# TYPEC.net
KiCad netlist of a schematic drawn in Altium Designer
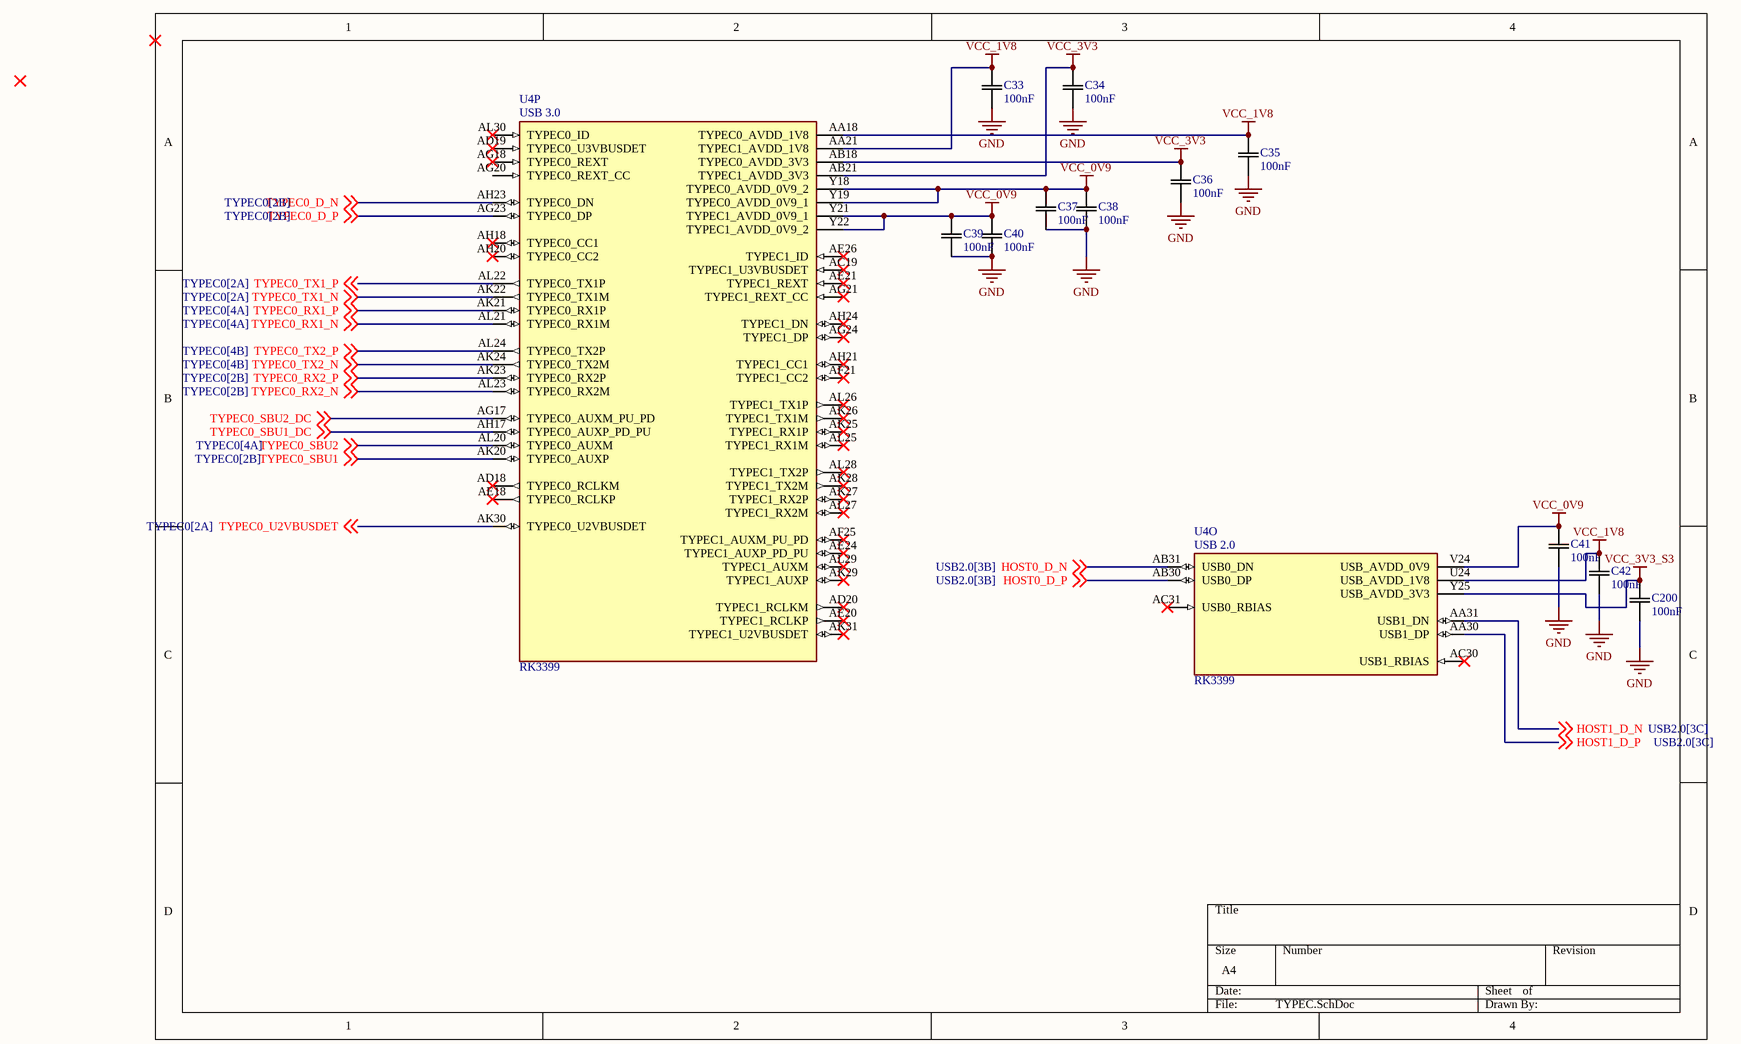
[diagram p0: TYPEC.SchDoc]

(export (version "E")
  (design (tool "Eeschema 10.0.6"))
  (components
    (comp (ref "C33")
      (value "100nF")
      (footprint "CAP_1005_TDK")
      (description "Description")
      (fields
        (field (name "MANUFACTURER_PART_NUMBER") "C1005X7R1H104M050BB")
        (field (name "COPYRIGHT") "Copyright (C) 2025 Ultra Librarian. All rights reserved.")
      )
      (libsource (lib "C1005X7R1H104M050BB") (part "C1005X7R1H104M050BB"))
    )
    (comp (ref "C34")
      (value "100nF")
      (footprint "CAP_1005_TDK")
      (description "Description")
      (fields
        (field (name "MANUFACTURER_PART_NUMBER") "C1005X7R1H104M050BB")
        (field (name "COPYRIGHT") "Copyright (C) 2025 Ultra Librarian. All rights reserved.")
      )
      (libsource (lib "C1005X7R1H104M050BB") (part "C1005X7R1H104M050BB"))
    )
    (comp (ref "C35")
      (value "100nF")
      (footprint "CAP_1005_TDK")
      (description "Description")
      (fields
        (field (name "MANUFACTURER_PART_NUMBER") "C1005X7R1H104M050BB")
        (field (name "COPYRIGHT") "Copyright (C) 2025 Ultra Librarian. All rights reserved.")
      )
      (libsource (lib "C1005X7R1H104M050BB") (part "C1005X7R1H104M050BB"))
    )
    (comp (ref "C36")
      (value "100nF")
      (footprint "CAP_1005_TDK")
      (description "Description")
      (fields
        (field (name "MANUFACTURER_PART_NUMBER") "C1005X7R1H104M050BB")
        (field (name "COPYRIGHT") "Copyright (C) 2025 Ultra Librarian. All rights reserved.")
      )
      (libsource (lib "C1005X7R1H104M050BB") (part "C1005X7R1H104M050BB"))
    )
    (comp (ref "C37")
      (value "100nF")
      (footprint "CAP_1005_TDK")
      (description "Description")
      (fields
        (field (name "MANUFACTURER_PART_NUMBER") "C1005X7R1H104M050BB")
        (field (name "COPYRIGHT") "Copyright (C) 2025 Ultra Librarian. All rights reserved.")
      )
      (libsource (lib "C1005X7R1H104M050BB") (part "C1005X7R1H104M050BB"))
    )
    (comp (ref "C38")
      (value "100nF")
      (footprint "CAP_1005_TDK")
      (description "Description")
      (fields
        (field (name "MANUFACTURER_PART_NUMBER") "C1005X7R1H104M050BB")
        (field (name "COPYRIGHT") "Copyright (C) 2025 Ultra Librarian. All rights reserved.")
      )
      (libsource (lib "C1005X7R1H104M050BB") (part "C1005X7R1H104M050BB"))
    )
    (comp (ref "C39")
      (value "100nF")
      (footprint "CAP_1005_TDK")
      (description "Description")
      (fields
        (field (name "MANUFACTURER_PART_NUMBER") "C1005X7R1H104M050BB")
        (field (name "COPYRIGHT") "Copyright (C) 2025 Ultra Librarian. All rights reserved.")
      )
      (libsource (lib "C1005X7R1H104M050BB") (part "C1005X7R1H104M050BB"))
    )
    (comp (ref "C40")
      (value "100nF")
      (footprint "CAP_1005_TDK")
      (description "Description")
      (fields
        (field (name "MANUFACTURER_PART_NUMBER") "C1005X7R1H104M050BB")
        (field (name "COPYRIGHT") "Copyright (C) 2025 Ultra Librarian. All rights reserved.")
      )
      (libsource (lib "C1005X7R1H104M050BB") (part "C1005X7R1H104M050BB"))
    )
    (comp (ref "C41")
      (value "100nF")
      (footprint "CAP_1005_TDK")
      (description "Description")
      (fields
        (field (name "MANUFACTURER_PART_NUMBER") "C1005X7R1H104M050BB")
        (field (name "COPYRIGHT") "Copyright (C) 2025 Ultra Librarian. All rights reserved.")
      )
      (libsource (lib "C1005X7R1H104M050BB") (part "C1005X7R1H104M050BB"))
    )
    (comp (ref "C42")
      (value "100nF")
      (footprint "CAP_1005_TDK")
      (description "Description")
      (fields
        (field (name "MANUFACTURER_PART_NUMBER") "C1005X7R1H104M050BB")
        (field (name "COPYRIGHT") "Copyright (C) 2025 Ultra Librarian. All rights reserved.")
      )
      (libsource (lib "C1005X7R1H104M050BB") (part "C1005X7R1H104M050BB"))
    )
    (comp (ref "C200")
      (value "100nF")
      (footprint "CAP_1005_TDK")
      (description "Description")
      (fields
        (field (name "MANUFACTURER_PART_NUMBER") "C1005X7R1H104M050BB")
        (field (name "COPYRIGHT") "Copyright (C) 2025 Ultra Librarian. All rights reserved.")
      )
      (libsource (lib "C1005X7R1H104M050BB") (part "C1005X7R1H104M050BB"))
    )
    (comp (ref "U4")
      (value "RK3399")
      (footprint "BGA828C65P31X31_2100X2100X161N")
      (description "RK3399 ROCK Pi 4 Model A 2GB - ARMÂ® CortexÂ®-A53, CortexÂ®-A72 MPU Embedded Evaluation Board")
      (fields (field (name "MF") "Rockchip"))
      (libsource (lib "RK3399") (part "RK3399"))
    )
  )
  (nets
    (net (code "1") (name "GND") (class "Default")
      (node (ref "C200") (pin "2") (pinfunction "2_2") (pintype "passive"))
      (node (ref "C33") (pin "2") (pinfunction "2_2") (pintype "passive"))
      (node (ref "C34") (pin "2") (pinfunction "2_2") (pintype "passive"))
      (node (ref "C35") (pin "2") (pinfunction "2_2") (pintype "passive"))
      (node (ref "C36") (pin "2") (pinfunction "2_2") (pintype "passive"))
      (node (ref "C37") (pin "2") (pinfunction "2_2") (pintype "passive"))
      (node (ref "C38") (pin "2") (pinfunction "2_2") (pintype "passive"))
      (node (ref "C39") (pin "2") (pinfunction "2_2") (pintype "passive"))
      (node (ref "C40") (pin "2") (pinfunction "2_2") (pintype "passive"))
      (node (ref "C41") (pin "2") (pinfunction "2_2") (pintype "passive"))
      (node (ref "C42") (pin "2") (pinfunction "2_2") (pintype "passive"))
    )
    (net (code "2") (name "HOST0_D_N") (class "Default")
      (node (ref "U4") (pin "AB31") (pinfunction "USB0_DN_AB31") (pintype "bidirectional"))
    )
    (net (code "3") (name "HOST0_D_P") (class "Default")
      (node (ref "U4") (pin "AB30") (pinfunction "USB0_DP_AB30") (pintype "bidirectional"))
    )
    (net (code "4") (name "HOST1_D_N") (class "Default")
      (node (ref "U4") (pin "AA31") (pinfunction "USB1_DN_AA31") (pintype "bidirectional"))
    )
    (net (code "5") (name "HOST1_D_P") (class "Default")
      (node (ref "U4") (pin "AA30") (pinfunction "USB1_DP_AA30") (pintype "bidirectional"))
    )
    (net (code "6") (name "TYPEC0_D_N") (class "Default")
      (node (ref "U4") (pin "AH23") (pinfunction "TYPEC0_DN_AH23") (pintype "bidirectional"))
    )
    (net (code "7") (name "TYPEC0_D_P") (class "Default")
      (node (ref "U4") (pin "AG23") (pinfunction "TYPEC0_DP_AG23") (pintype "bidirectional"))
    )
    (net (code "8") (name "TYPEC0_RX1_N") (class "Default")
      (node (ref "U4") (pin "AL21") (pinfunction "TYPEC0_RX1M_AL21") (pintype "bidirectional"))
    )
    (net (code "9") (name "TYPEC0_RX1_P") (class "Default")
      (node (ref "U4") (pin "AK21") (pinfunction "TYPEC0_RX1P_AK21") (pintype "bidirectional"))
    )
    (net (code "10") (name "TYPEC0_RX2_N") (class "Default")
      (node (ref "U4") (pin "AL23") (pinfunction "TYPEC0_RX2M_AL23") (pintype "bidirectional"))
    )
    (net (code "11") (name "TYPEC0_RX2_P") (class "Default")
      (node (ref "U4") (pin "AK23") (pinfunction "TYPEC0_RX2P_AK23") (pintype "bidirectional"))
    )
    (net (code "12") (name "TYPEC0_SBU1") (class "Default")
      (node (ref "U4") (pin "AK20") (pinfunction "TYPEC0_AUXP_AK20") (pintype "bidirectional"))
    )
    (net (code "13") (name "TYPEC0_SBU1_DC") (class "Default")
      (node (ref "U4") (pin "AH17") (pinfunction "TYPEC0_AUXP_PD_PU_AH17") (pintype "bidirectional"))
    )
    (net (code "14") (name "TYPEC0_SBU2") (class "Default")
      (node (ref "U4") (pin "AL20") (pinfunction "TYPEC0_AUXM_AL20") (pintype "bidirectional"))
    )
    (net (code "15") (name "TYPEC0_SBU2_DC") (class "Default")
      (node (ref "U4") (pin "AG17") (pinfunction "TYPEC0_AUXM_PU_PD_AG17") (pintype "bidirectional"))
    )
    (net (code "16") (name "TYPEC0_TX1_N") (class "Default")
      (node (ref "U4") (pin "AK22") (pinfunction "TYPEC0_TX1M_AK22") (pintype "output"))
    )
    (net (code "17") (name "TYPEC0_TX1_P") (class "Default")
      (node (ref "U4") (pin "AL22") (pinfunction "TYPEC0_TX1P_AL22") (pintype "output"))
    )
    (net (code "18") (name "TYPEC0_TX2_N") (class "Default")
      (node (ref "U4") (pin "AK24") (pinfunction "TYPEC0_TX2M_AK24") (pintype "output"))
    )
    (net (code "19") (name "TYPEC0_TX2_P") (class "Default")
      (node (ref "U4") (pin "AL24") (pinfunction "TYPEC0_TX2P_AL24") (pintype "output"))
    )
    (net (code "20") (name "TYPEC0_U2VBUSDET") (class "Default")
      (node (ref "U4") (pin "AK30") (pinfunction "TYPEC0_U2VBUSDET_AK30") (pintype "bidirectional"))
    )
    (net (code "21") (name "VCC_0V9") (class "Default")
      (node (ref "C37") (pin "1") (pinfunction "1_1") (pintype "passive"))
      (node (ref "C38") (pin "1") (pinfunction "1_1") (pintype "passive"))
      (node (ref "C39") (pin "1") (pinfunction "1_1") (pintype "passive"))
      (node (ref "C40") (pin "1") (pinfunction "1_1") (pintype "passive"))
      (node (ref "C41") (pin "1") (pinfunction "1_1") (pintype "passive"))
      (node (ref "U4") (pin "V24") (pinfunction "USB_AVDD_0V9_V24") (pintype "power_in"))
      (node (ref "U4") (pin "Y18") (pinfunction "TYPEC0_AVDD_0V9_2_Y18") (pintype "power_in"))
      (node (ref "U4") (pin "Y19") (pinfunction "TYPEC0_AVDD_0V9_1_Y19") (pintype "power_in"))
      (node (ref "U4") (pin "Y21") (pinfunction "TYPEC1_AVDD_0V9_1_Y21") (pintype "power_in"))
      (node (ref "U4") (pin "Y22") (pinfunction "TYPEC1_AVDD_0V9_2_Y22") (pintype "power_in"))
    )
    (net (code "22") (name "VCC_1V8") (class "Default")
      (node (ref "C33") (pin "1") (pinfunction "1_1") (pintype "passive"))
      (node (ref "C35") (pin "1") (pinfunction "1_1") (pintype "passive"))
      (node (ref "C42") (pin "1") (pinfunction "1_1") (pintype "passive"))
      (node (ref "U4") (pin "AA18") (pinfunction "TYPEC0_AVDD_1V8_AA18") (pintype "power_in"))
      (node (ref "U4") (pin "AA21") (pinfunction "TYPEC1_AVDD_1V8_AA21") (pintype "power_in"))
      (node (ref "U4") (pin "U24") (pinfunction "USB_AVDD_1V8_U24") (pintype "power_in"))
    )
    (net (code "23") (name "VCC_3V3") (class "Default")
      (node (ref "C34") (pin "1") (pinfunction "1_1") (pintype "passive"))
      (node (ref "C36") (pin "1") (pinfunction "1_1") (pintype "passive"))
      (node (ref "U4") (pin "AB18") (pinfunction "TYPEC0_AVDD_3V3_AB18") (pintype "power_in"))
      (node (ref "U4") (pin "AB21") (pinfunction "TYPEC1_AVDD_3V3_AB21") (pintype "power_in"))
    )
    (net (code "24") (name "VCC_3V3_S3") (class "Default")
      (node (ref "C200") (pin "1") (pinfunction "1_1") (pintype "passive"))
      (node (ref "U4") (pin "Y25") (pinfunction "USB_AVDD_3V3_Y25") (pintype "power_in"))
    )
    (net (code "25") (name "unconnected-(U4O-USB0_RBIAS-PadAC31)") (class "Default")
      (node (ref "U4") (pin "AC31") (pinfunction "USB0_RBIAS_AC31") (pintype "input+no_connect"))
    )
    (net (code "26") (name "unconnected-(U4O-USB1_RBIAS-PadAC30)") (class "Default")
      (node (ref "U4") (pin "AC30") (pinfunction "USB1_RBIAS_AC30") (pintype "input+no_connect"))
    )
    (net (code "27") (name "unconnected-(U4P-TYPEC0_CC1-PadAH18)") (class "Default")
      (node (ref "U4") (pin "AH18") (pinfunction "TYPEC0_CC1_AH18") (pintype "bidirectional+no_connect"))
    )
    (net (code "28") (name "unconnected-(U4P-TYPEC0_CC2-PadAH20)") (class "Default")
      (node (ref "U4") (pin "AH20") (pinfunction "TYPEC0_CC2_AH20") (pintype "bidirectional+no_connect"))
    )
    (net (code "29") (name "unconnected-(U4P-TYPEC0_ID-PadAL30)") (class "Default")
      (node (ref "U4") (pin "AL30") (pinfunction "TYPEC0_ID_AL30") (pintype "input+no_connect"))
    )
    (net (code "30") (name "unconnected-(U4P-TYPEC0_RCLKM-PadAD18)") (class "Default")
      (node (ref "U4") (pin "AD18") (pinfunction "TYPEC0_RCLKM_AD18") (pintype "output+no_connect"))
    )
    (net (code "31") (name "unconnected-(U4P-TYPEC0_RCLKP-PadAE18)") (class "Default")
      (node (ref "U4") (pin "AE18") (pinfunction "TYPEC0_RCLKP_AE18") (pintype "output+no_connect"))
    )
    (net (code "32") (name "unconnected-(U4P-TYPEC0_REXT-PadAG18)") (class "Default")
      (node (ref "U4") (pin "AG18") (pinfunction "TYPEC0_REXT_AG18") (pintype "input+no_connect"))
    )
    (net (code "33") (name "unconnected-(U4P-TYPEC0_REXT_CC-PadAG20)") (class "Default")
      (node (ref "U4") (pin "AG20") (pinfunction "TYPEC0_REXT_CC_AG20") (pintype "input"))
    )
    (net (code "34") (name "unconnected-(U4P-TYPEC0_U3VBUSDET-PadAD19)") (class "Default")
      (node (ref "U4") (pin "AD19") (pinfunction "TYPEC0_U3VBUSDET_AD19") (pintype "input+no_connect"))
    )
    (net (code "35") (name "unconnected-(U4P-TYPEC1_AUXM-PadAL29)") (class "Default")
      (node (ref "U4") (pin "AL29") (pinfunction "TYPEC1_AUXM_AL29") (pintype "bidirectional+no_connect"))
    )
    (net (code "36") (name "unconnected-(U4P-TYPEC1_AUXM_PU_PD-PadAF25)") (class "Default")
      (node (ref "U4") (pin "AF25") (pinfunction "TYPEC1_AUXM_PU_PD_AF25") (pintype "bidirectional+no_connect"))
    )
    (net (code "37") (name "unconnected-(U4P-TYPEC1_AUXP-PadAK29)") (class "Default")
      (node (ref "U4") (pin "AK29") (pinfunction "TYPEC1_AUXP_AK29") (pintype "bidirectional+no_connect"))
    )
    (net (code "38") (name "unconnected-(U4P-TYPEC1_AUXP_PD_PU-PadAE24)") (class "Default")
      (node (ref "U4") (pin "AE24") (pinfunction "TYPEC1_AUXP_PD_PU_AE24") (pintype "bidirectional+no_connect"))
    )
    (net (code "39") (name "unconnected-(U4P-TYPEC1_CC1-PadAH21)") (class "Default")
      (node (ref "U4") (pin "AH21") (pinfunction "TYPEC1_CC1_AH21") (pintype "bidirectional+no_connect"))
    )
    (net (code "40") (name "unconnected-(U4P-TYPEC1_CC2-PadAF21)") (class "Default")
      (node (ref "U4") (pin "AF21") (pinfunction "TYPEC1_CC2_AF21") (pintype "bidirectional+no_connect"))
    )
    (net (code "41") (name "unconnected-(U4P-TYPEC1_DN-PadAH24)") (class "Default")
      (node (ref "U4") (pin "AH24") (pinfunction "TYPEC1_DN_AH24") (pintype "bidirectional+no_connect"))
    )
    (net (code "42") (name "unconnected-(U4P-TYPEC1_DP-PadAG24)") (class "Default")
      (node (ref "U4") (pin "AG24") (pinfunction "TYPEC1_DP_AG24") (pintype "bidirectional+no_connect"))
    )
    (net (code "43") (name "unconnected-(U4P-TYPEC1_ID-PadAE26)") (class "Default")
      (node (ref "U4") (pin "AE26") (pinfunction "TYPEC1_ID_AE26") (pintype "input+no_connect"))
    )
    (net (code "44") (name "unconnected-(U4P-TYPEC1_RCLKM-PadAD20)") (class "Default")
      (node (ref "U4") (pin "AD20") (pinfunction "TYPEC1_RCLKM_AD20") (pintype "output+no_connect"))
    )
    (net (code "45") (name "unconnected-(U4P-TYPEC1_RCLKP-PadAE20)") (class "Default")
      (node (ref "U4") (pin "AE20") (pinfunction "TYPEC1_RCLKP_AE20") (pintype "output+no_connect"))
    )
    (net (code "46") (name "unconnected-(U4P-TYPEC1_REXT-PadAE21)") (class "Default")
      (node (ref "U4") (pin "AE21") (pinfunction "TYPEC1_REXT_AE21") (pintype "input+no_connect"))
    )
    (net (code "47") (name "unconnected-(U4P-TYPEC1_REXT_CC-PadAG21)") (class "Default")
      (node (ref "U4") (pin "AG21") (pinfunction "TYPEC1_REXT_CC_AG21") (pintype "input+no_connect"))
    )
    (net (code "48") (name "unconnected-(U4P-TYPEC1_RX1M-PadAL25)") (class "Default")
      (node (ref "U4") (pin "AL25") (pinfunction "TYPEC1_RX1M_AL25") (pintype "bidirectional+no_connect"))
    )
    (net (code "49") (name "unconnected-(U4P-TYPEC1_RX1P-PadAK25)") (class "Default")
      (node (ref "U4") (pin "AK25") (pinfunction "TYPEC1_RX1P_AK25") (pintype "bidirectional+no_connect"))
    )
    (net (code "50") (name "unconnected-(U4P-TYPEC1_RX2M-PadAL27)") (class "Default")
      (node (ref "U4") (pin "AL27") (pinfunction "TYPEC1_RX2M_AL27") (pintype "bidirectional+no_connect"))
    )
    (net (code "51") (name "unconnected-(U4P-TYPEC1_RX2P-PadAK27)") (class "Default")
      (node (ref "U4") (pin "AK27") (pinfunction "TYPEC1_RX2P_AK27") (pintype "bidirectional+no_connect"))
    )
    (net (code "52") (name "unconnected-(U4P-TYPEC1_TX1M-PadAK26)") (class "Default")
      (node (ref "U4") (pin "AK26") (pinfunction "TYPEC1_TX1M_AK26") (pintype "output+no_connect"))
    )
    (net (code "53") (name "unconnected-(U4P-TYPEC1_TX1P-PadAL26)") (class "Default")
      (node (ref "U4") (pin "AL26") (pinfunction "TYPEC1_TX1P_AL26") (pintype "output+no_connect"))
    )
    (net (code "54") (name "unconnected-(U4P-TYPEC1_TX2M-PadAK28)") (class "Default")
      (node (ref "U4") (pin "AK28") (pinfunction "TYPEC1_TX2M_AK28") (pintype "output+no_connect"))
    )
    (net (code "55") (name "unconnected-(U4P-TYPEC1_TX2P-PadAL28)") (class "Default")
      (node (ref "U4") (pin "AL28") (pinfunction "TYPEC1_TX2P_AL28") (pintype "output+no_connect"))
    )
    (net (code "56") (name "unconnected-(U4P-TYPEC1_U2VBUSDET-PadAK31)") (class "Default")
      (node (ref "U4") (pin "AK31") (pinfunction "TYPEC1_U2VBUSDET_AK31") (pintype "bidirectional+no_connect"))
    )
    (net (code "57") (name "unconnected-(U4P-TYPEC1_U3VBUSDET-PadAC19)") (class "Default")
      (node (ref "U4") (pin "AC19") (pinfunction "TYPEC1_U3VBUSDET_AC19") (pintype "input+no_connect"))
    )
  )
)
